# UCube_v2_03.net
KiCad netlist of a schematic drawn in EAGLE
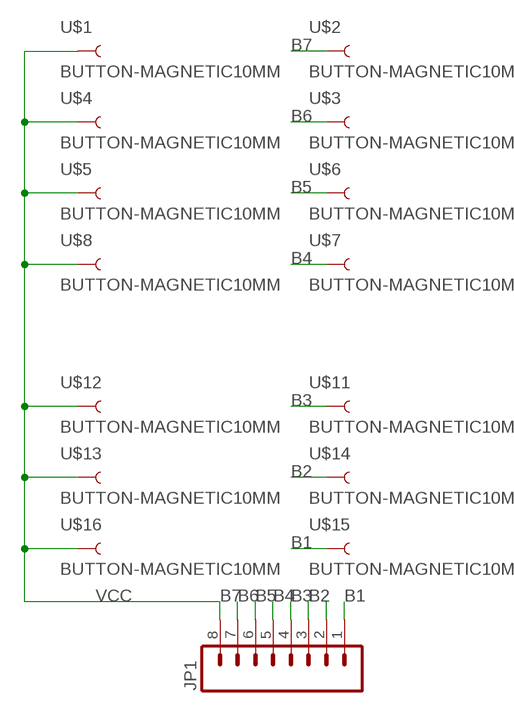
[diagram p0: schematic, sheet 1]

(export (version "E")
  (design (tool "Eeschema 10.0.6"))
  (components
    (comp (ref "JP1")
      (value "M081X08")
      (footprint "eagle-import:1X08")
      (libsource (lib "eagle-import") (part "M081X08"))
    )
    (comp (ref "U$1")
      (value "BUTTON-MAGNETIC10MM")
      (footprint "eagle-import:BUTTON-10MM")
      (libsource (lib "eagle-import") (part "BUTTON-MAGNETIC10MM"))
    )
    (comp (ref "U$2")
      (value "BUTTON-MAGNETIC10MM")
      (footprint "eagle-import:BUTTON-10MM")
      (libsource (lib "eagle-import") (part "BUTTON-MAGNETIC10MM"))
    )
    (comp (ref "U$3")
      (value "BUTTON-MAGNETIC10MM")
      (footprint "eagle-import:BUTTON-10MM")
      (libsource (lib "eagle-import") (part "BUTTON-MAGNETIC10MM"))
    )
    (comp (ref "U$4")
      (value "BUTTON-MAGNETIC10MM")
      (footprint "eagle-import:BUTTON-10MM")
      (libsource (lib "eagle-import") (part "BUTTON-MAGNETIC10MM"))
    )
    (comp (ref "U$5")
      (value "BUTTON-MAGNETIC10MM")
      (footprint "eagle-import:BUTTON-10MM")
      (libsource (lib "eagle-import") (part "BUTTON-MAGNETIC10MM"))
    )
    (comp (ref "U$6")
      (value "BUTTON-MAGNETIC10MM")
      (footprint "eagle-import:BUTTON-10MM")
      (libsource (lib "eagle-import") (part "BUTTON-MAGNETIC10MM"))
    )
    (comp (ref "U$7")
      (value "BUTTON-MAGNETIC10MM")
      (footprint "eagle-import:BUTTON-10MM")
      (libsource (lib "eagle-import") (part "BUTTON-MAGNETIC10MM"))
    )
    (comp (ref "U$8")
      (value "BUTTON-MAGNETIC10MM")
      (footprint "eagle-import:BUTTON-10MM")
      (libsource (lib "eagle-import") (part "BUTTON-MAGNETIC10MM"))
    )
    (comp (ref "U$11")
      (value "BUTTON-MAGNETIC10MM")
      (footprint "eagle-import:BUTTON-10MM")
      (libsource (lib "eagle-import") (part "BUTTON-MAGNETIC10MM"))
    )
    (comp (ref "U$12")
      (value "BUTTON-MAGNETIC10MM")
      (footprint "eagle-import:BUTTON-10MM")
      (libsource (lib "eagle-import") (part "BUTTON-MAGNETIC10MM"))
    )
    (comp (ref "U$13")
      (value "BUTTON-MAGNETIC10MM")
      (footprint "eagle-import:BUTTON-10MM")
      (libsource (lib "eagle-import") (part "BUTTON-MAGNETIC10MM"))
    )
    (comp (ref "U$14")
      (value "BUTTON-MAGNETIC10MM")
      (footprint "eagle-import:BUTTON-10MM")
      (libsource (lib "eagle-import") (part "BUTTON-MAGNETIC10MM"))
    )
    (comp (ref "U$15")
      (value "BUTTON-MAGNETIC10MM")
      (footprint "eagle-import:BUTTON-10MM")
      (libsource (lib "eagle-import") (part "BUTTON-MAGNETIC10MM"))
    )
    (comp (ref "U$16")
      (value "BUTTON-MAGNETIC10MM")
      (footprint "eagle-import:BUTTON-10MM")
      (libsource (lib "eagle-import") (part "BUTTON-MAGNETIC10MM"))
    )
  )
  (nets
    (net (code "1") (name "/B1") (class "Default")
      (node (ref "JP1") (pin "1") (pinfunction "1_1") (pintype "passive"))
      (node (ref "U$15") (pin "1") (pinfunction "1_1") (pintype "bidirectional"))
    )
    (net (code "2") (name "/B2") (class "Default")
      (node (ref "JP1") (pin "2") (pinfunction "2_2") (pintype "passive"))
      (node (ref "U$14") (pin "1") (pinfunction "1_1") (pintype "bidirectional"))
    )
    (net (code "3") (name "/B3") (class "Default")
      (node (ref "JP1") (pin "3") (pinfunction "3_3") (pintype "passive"))
      (node (ref "U$11") (pin "1") (pinfunction "1_1") (pintype "bidirectional"))
    )
    (net (code "4") (name "/B4") (class "Default")
      (node (ref "JP1") (pin "4") (pinfunction "4_4") (pintype "passive"))
      (node (ref "U$7") (pin "1") (pinfunction "1_1") (pintype "bidirectional"))
    )
    (net (code "5") (name "/B5") (class "Default")
      (node (ref "JP1") (pin "5") (pinfunction "5_5") (pintype "passive"))
      (node (ref "U$6") (pin "1") (pinfunction "1_1") (pintype "bidirectional"))
    )
    (net (code "6") (name "/B6") (class "Default")
      (node (ref "JP1") (pin "6") (pinfunction "6_6") (pintype "passive"))
      (node (ref "U$3") (pin "1") (pinfunction "1_1") (pintype "bidirectional"))
    )
    (net (code "7") (name "/B7") (class "Default")
      (node (ref "JP1") (pin "7") (pinfunction "7_7") (pintype "passive"))
      (node (ref "U$2") (pin "1") (pinfunction "1_1") (pintype "bidirectional"))
    )
    (net (code "8") (name "/VCC") (class "Default")
      (node (ref "JP1") (pin "8") (pinfunction "8_8") (pintype "passive"))
      (node (ref "U$1") (pin "1") (pinfunction "1_1") (pintype "bidirectional"))
      (node (ref "U$12") (pin "1") (pinfunction "1_1") (pintype "bidirectional"))
      (node (ref "U$13") (pin "1") (pinfunction "1_1") (pintype "bidirectional"))
      (node (ref "U$16") (pin "1") (pinfunction "1_1") (pintype "bidirectional"))
      (node (ref "U$4") (pin "1") (pinfunction "1_1") (pintype "bidirectional"))
      (node (ref "U$5") (pin "1") (pinfunction "1_1") (pintype "bidirectional"))
      (node (ref "U$8") (pin "1") (pinfunction "1_1") (pintype "bidirectional"))
    )
  )
)
